# DINv2_1.net
KiCad netlist of a schematic drawn in EAGLE
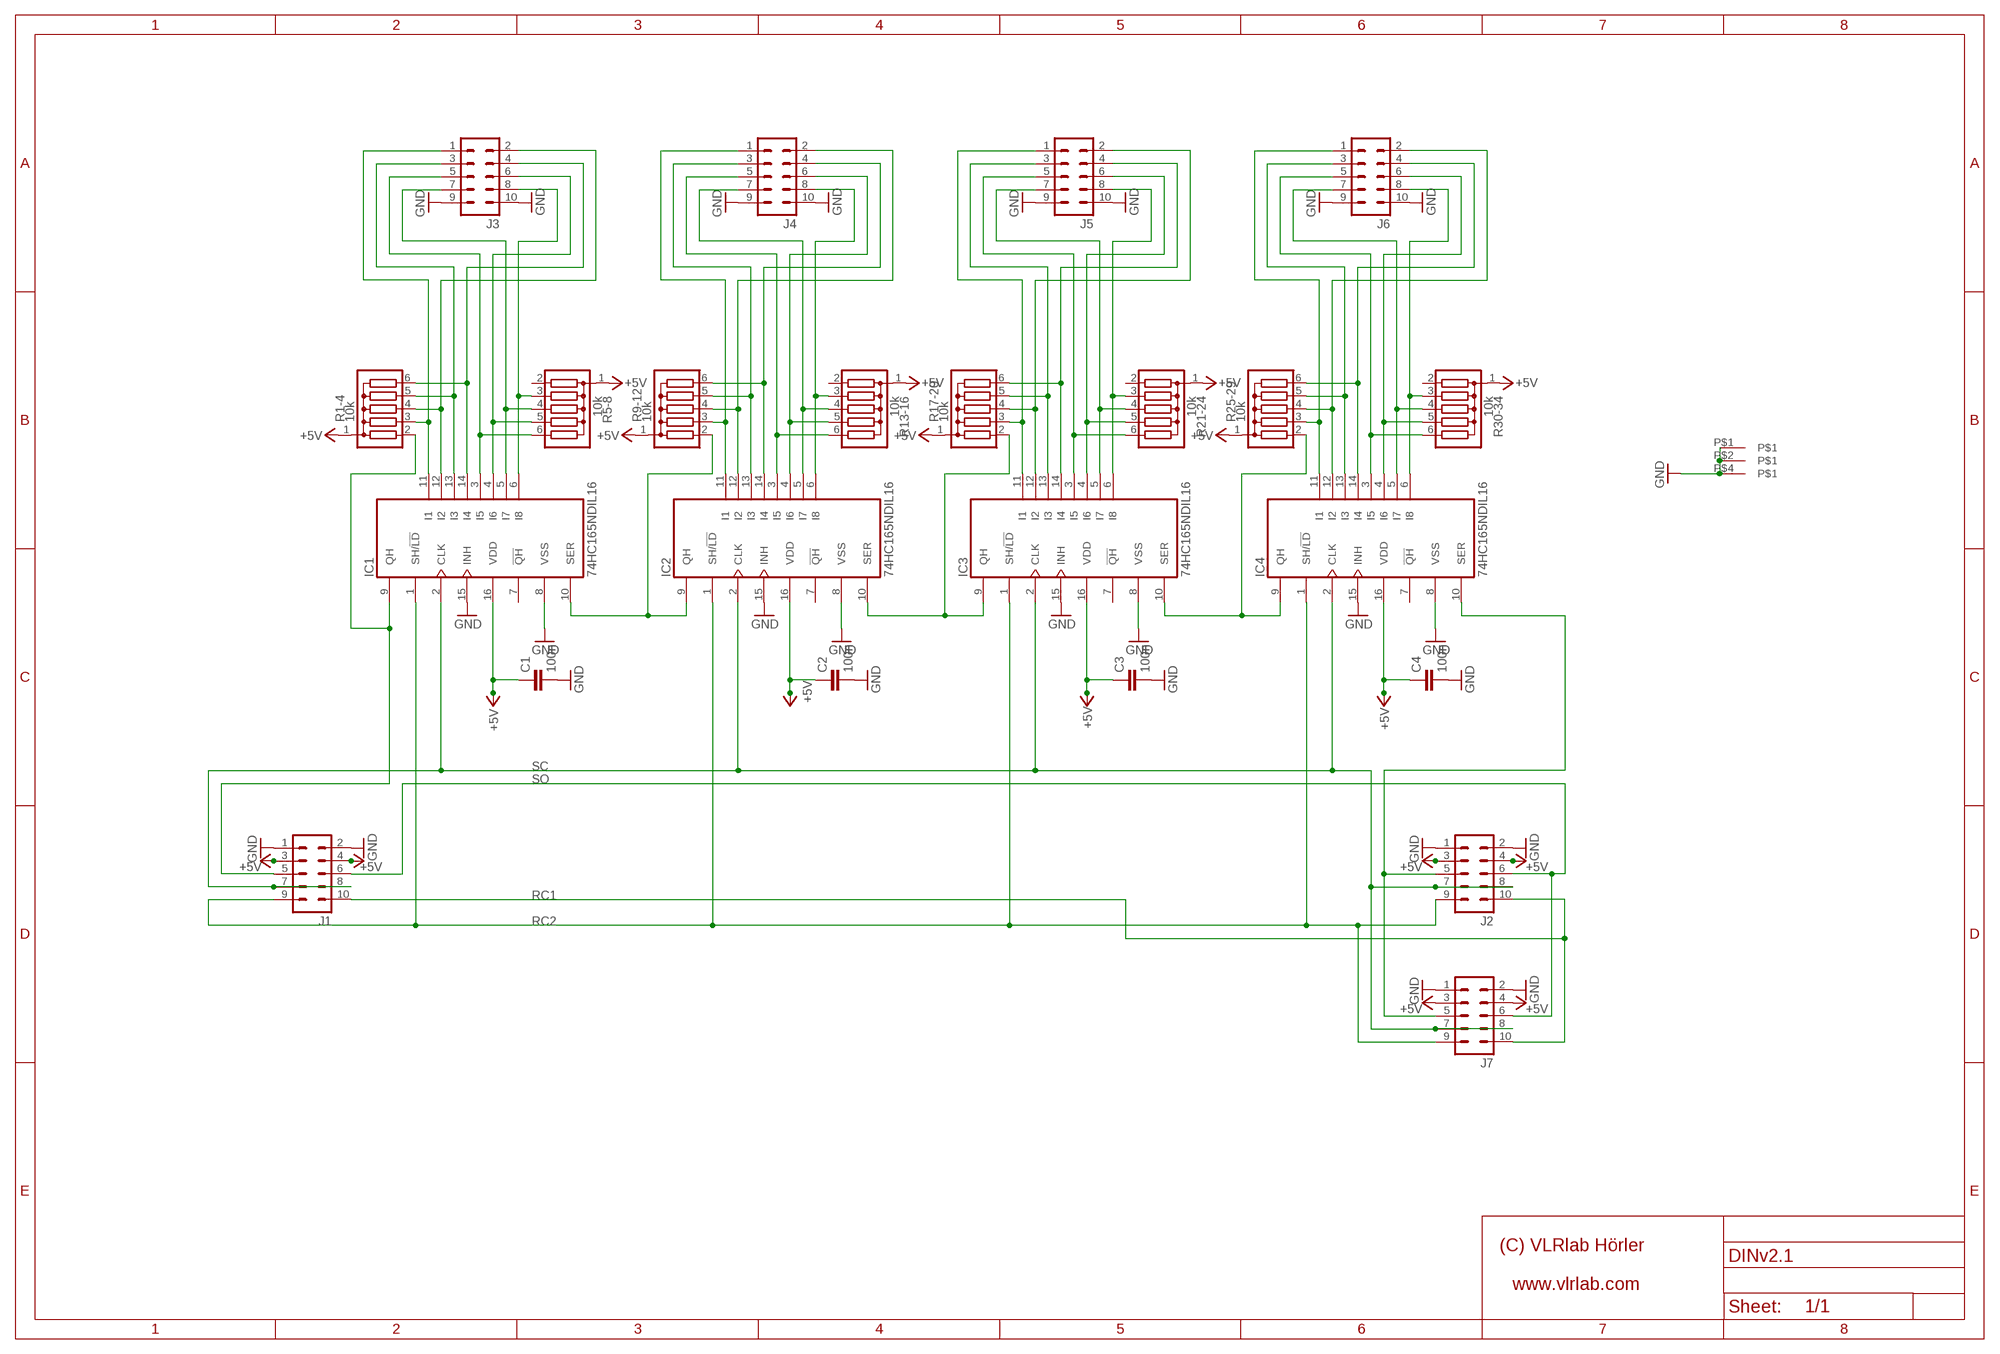
[diagram p0: schematic, sheet 1]

(export (version "E")
  (design (tool "Eeschema 10.0.6"))
  (components
    (comp (ref "C1")
      (value "100n")
      (footprint "eagle-import:C025-025X050")
      (libsource (lib "eagle-import") (part "C-EU025-025X050"))
    )
    (comp (ref "C2")
      (value "100n")
      (footprint "eagle-import:C025-025X050")
      (libsource (lib "eagle-import") (part "C-EU025-025X050"))
    )
    (comp (ref "C3")
      (value "100n")
      (footprint "eagle-import:C025-025X050")
      (libsource (lib "eagle-import") (part "C-EU025-025X050"))
    )
    (comp (ref "C4")
      (value "100n")
      (footprint "eagle-import:C025-025X050")
      (libsource (lib "eagle-import") (part "C-EU025-025X050"))
    )
    (comp (ref "IC1")
      (value "74HC165NDIL16")
      (footprint "eagle-import:DIL16")
      (libsource (lib "eagle-import") (part "74HC165NDIL16"))
    )
    (comp (ref "IC2")
      (value "74HC165NDIL16")
      (footprint "eagle-import:DIL16")
      (libsource (lib "eagle-import") (part "74HC165NDIL16"))
    )
    (comp (ref "IC3")
      (value "74HC165NDIL16")
      (footprint "eagle-import:DIL16")
      (libsource (lib "eagle-import") (part "74HC165NDIL16"))
    )
    (comp (ref "IC4")
      (value "74HC165NDIL16")
      (footprint "eagle-import:DIL16")
      (libsource (lib "eagle-import") (part "74HC165NDIL16"))
    )
    (comp (ref "J1")
      (value "ML10")
      (footprint "eagle-import:ML10")
      (libsource (lib "eagle-import") (part "ML10"))
    )
    (comp (ref "J2")
      (value "ML10")
      (footprint "eagle-import:ML10")
      (libsource (lib "eagle-import") (part "ML10"))
    )
    (comp (ref "J3")
      (value "ML10")
      (footprint "eagle-import:ML10")
      (libsource (lib "eagle-import") (part "ML10"))
    )
    (comp (ref "J4")
      (value "ML10")
      (footprint "eagle-import:ML10")
      (libsource (lib "eagle-import") (part "ML10"))
    )
    (comp (ref "J5")
      (value "ML10")
      (footprint "eagle-import:ML10")
      (libsource (lib "eagle-import") (part "ML10"))
    )
    (comp (ref "J6")
      (value "ML10")
      (footprint "eagle-import:ML10")
      (libsource (lib "eagle-import") (part "ML10"))
    )
    (comp (ref "J7")
      (value "ML10")
      (footprint "eagle-import:ML10")
      (libsource (lib "eagle-import") (part "ML10"))
    )
    (comp (ref "R1-4")
      (value "10k")
      (footprint "eagle-import:SIL6")
      (libsource (lib "eagle-import") (part "4306R"))
    )
    (comp (ref "R5-8")
      (value "10k")
      (footprint "eagle-import:SIL6")
      (libsource (lib "eagle-import") (part "4306R"))
    )
    (comp (ref "R9-12")
      (value "10k")
      (footprint "eagle-import:SIL6")
      (libsource (lib "eagle-import") (part "4306R"))
    )
    (comp (ref "R13-16")
      (value "10k")
      (footprint "eagle-import:SIL6")
      (libsource (lib "eagle-import") (part "4306R"))
    )
    (comp (ref "R17-20")
      (value "10k")
      (footprint "eagle-import:SIL6")
      (libsource (lib "eagle-import") (part "4306R"))
    )
    (comp (ref "R21-24")
      (value "10k")
      (footprint "eagle-import:SIL6")
      (libsource (lib "eagle-import") (part "4306R"))
    )
    (comp (ref "R25-29")
      (value "10k")
      (footprint "eagle-import:SIL6")
      (libsource (lib "eagle-import") (part "4306R"))
    )
    (comp (ref "R30-34")
      (value "10k")
      (footprint "eagle-import:SIL6")
      (libsource (lib "eagle-import") (part "4306R"))
    )
    (comp (ref "U$7")
      (value "MIDIBOX_HALF")
      (footprint "eagle-import:MIDIBOX14X6")
      (libsource (lib "eagle-import") (part "MIDIBOX_HALF"))
    )
  )
  (nets
    (net (code "1") (name "+5V") (class "Default")
      (node (ref "C1") (pin "1") (pinfunction "1_1") (pintype "passive"))
      (node (ref "C2") (pin "1") (pinfunction "1_1") (pintype "passive"))
      (node (ref "C3") (pin "1") (pinfunction "1_1") (pintype "passive"))
      (node (ref "C4") (pin "1") (pinfunction "1_1") (pintype "passive"))
      (node (ref "IC1") (pin "16") (pinfunction "VDD_16") (pintype "power_in"))
      (node (ref "IC2") (pin "16") (pinfunction "VDD_16") (pintype "power_in"))
      (node (ref "IC3") (pin "16") (pinfunction "VDD_16") (pintype "power_in"))
      (node (ref "IC4") (pin "16") (pinfunction "VDD_16") (pintype "power_in"))
      (node (ref "J1") (pin "3") (pinfunction "3_3") (pintype "passive"))
      (node (ref "J1") (pin "4") (pinfunction "4_4") (pintype "passive"))
      (node (ref "J2") (pin "3") (pinfunction "3_3") (pintype "passive"))
      (node (ref "J2") (pin "4") (pinfunction "4_4") (pintype "passive"))
      (node (ref "J7") (pin "3") (pinfunction "3_3") (pintype "passive"))
      (node (ref "J7") (pin "4") (pinfunction "4_4") (pintype "passive"))
      (node (ref "R1-4") (pin "1") (pinfunction "1_1") (pintype "passive"))
      (node (ref "R13-16") (pin "1") (pinfunction "1_1") (pintype "passive"))
      (node (ref "R17-20") (pin "1") (pinfunction "1_1") (pintype "passive"))
      (node (ref "R21-24") (pin "1") (pinfunction "1_1") (pintype "passive"))
      (node (ref "R25-29") (pin "1") (pinfunction "1_1") (pintype "passive"))
      (node (ref "R30-34") (pin "1") (pinfunction "1_1") (pintype "passive"))
      (node (ref "R5-8") (pin "1") (pinfunction "1_1") (pintype "passive"))
      (node (ref "R9-12") (pin "1") (pinfunction "1_1") (pintype "passive"))
    )
    (net (code "2") (name "/RC1") (class "Default")
      (node (ref "J1") (pin "10") (pinfunction "10_10") (pintype "passive"))
      (node (ref "J2") (pin "10") (pinfunction "10_10") (pintype "passive"))
      (node (ref "J7") (pin "10") (pinfunction "10_10") (pintype "passive"))
    )
    (net (code "3") (name "/RC2") (class "Default")
      (node (ref "IC1") (pin "1") (pinfunction "SH/~{LD}_1") (pintype "input"))
      (node (ref "IC2") (pin "1") (pinfunction "SH/~{LD}_1") (pintype "input"))
      (node (ref "IC3") (pin "1") (pinfunction "SH/~{LD}_1") (pintype "input"))
      (node (ref "IC4") (pin "1") (pinfunction "SH/~{LD}_1") (pintype "input"))
      (node (ref "J1") (pin "9") (pinfunction "9_9") (pintype "passive"))
      (node (ref "J2") (pin "9") (pinfunction "9_9") (pintype "passive"))
      (node (ref "J7") (pin "9") (pinfunction "9_9") (pintype "passive"))
    )
    (net (code "4") (name "/SC") (class "Default")
      (node (ref "IC1") (pin "2") (pinfunction "CLK_2") (pintype "input"))
      (node (ref "IC2") (pin "2") (pinfunction "CLK_2") (pintype "input"))
      (node (ref "IC3") (pin "2") (pinfunction "CLK_2") (pintype "input"))
      (node (ref "IC4") (pin "2") (pinfunction "CLK_2") (pintype "input"))
      (node (ref "J1") (pin "7") (pinfunction "7_7") (pintype "passive"))
      (node (ref "J1") (pin "8") (pinfunction "8_8") (pintype "passive"))
      (node (ref "J2") (pin "7") (pinfunction "7_7") (pintype "passive"))
      (node (ref "J2") (pin "8") (pinfunction "8_8") (pintype "passive"))
      (node (ref "J7") (pin "7") (pinfunction "7_7") (pintype "passive"))
      (node (ref "J7") (pin "8") (pinfunction "8_8") (pintype "passive"))
    )
    (net (code "5") (name "/SO") (class "Default")
      (node (ref "J1") (pin "6") (pinfunction "6_6") (pintype "passive"))
      (node (ref "J2") (pin "6") (pinfunction "6_6") (pintype "passive"))
      (node (ref "J7") (pin "6") (pinfunction "6_6") (pintype "passive"))
    )
    (net (code "6") (name "GND") (class "Default")
      (node (ref "C1") (pin "2") (pinfunction "2_2") (pintype "passive"))
      (node (ref "C2") (pin "2") (pinfunction "2_2") (pintype "passive"))
      (node (ref "C3") (pin "2") (pinfunction "2_2") (pintype "passive"))
      (node (ref "C4") (pin "2") (pinfunction "2_2") (pintype "passive"))
      (node (ref "IC1") (pin "15") (pinfunction "INH_15") (pintype "input"))
      (node (ref "IC1") (pin "8") (pinfunction "VSS_8") (pintype "power_in"))
      (node (ref "IC2") (pin "15") (pinfunction "INH_15") (pintype "input"))
      (node (ref "IC2") (pin "8") (pinfunction "VSS_8") (pintype "power_in"))
      (node (ref "IC3") (pin "15") (pinfunction "INH_15") (pintype "input"))
      (node (ref "IC3") (pin "8") (pinfunction "VSS_8") (pintype "power_in"))
      (node (ref "IC4") (pin "15") (pinfunction "INH_15") (pintype "input"))
      (node (ref "IC4") (pin "8") (pinfunction "VSS_8") (pintype "power_in"))
      (node (ref "J1") (pin "1") (pinfunction "1_1") (pintype "passive"))
      (node (ref "J1") (pin "2") (pinfunction "2_2") (pintype "passive"))
      (node (ref "J2") (pin "1") (pinfunction "1_1") (pintype "passive"))
      (node (ref "J2") (pin "2") (pinfunction "2_2") (pintype "passive"))
      (node (ref "J3") (pin "10") (pinfunction "10_10") (pintype "passive"))
      (node (ref "J3") (pin "9") (pinfunction "9_9") (pintype "passive"))
      (node (ref "J4") (pin "10") (pinfunction "10_10") (pintype "passive"))
      (node (ref "J4") (pin "9") (pinfunction "9_9") (pintype "passive"))
      (node (ref "J5") (pin "10") (pinfunction "10_10") (pintype "passive"))
      (node (ref "J5") (pin "9") (pinfunction "9_9") (pintype "passive"))
      (node (ref "J6") (pin "10") (pinfunction "10_10") (pintype "passive"))
      (node (ref "J6") (pin "9") (pinfunction "9_9") (pintype "passive"))
      (node (ref "J7") (pin "1") (pinfunction "1_1") (pintype "passive"))
      (node (ref "J7") (pin "2") (pinfunction "2_2") (pintype "passive"))
      (node (ref "U$7") (pin "P$1") (pinfunction "P$1_P$1") (pintype "bidirectional"))
      (node (ref "U$7") (pin "P$2") (pinfunction "P$1_P$2") (pintype "bidirectional"))
      (node (ref "U$7") (pin "P$4") (pinfunction "P$1_P$4") (pintype "bidirectional"))
    )
    (net (code "7") (name "Net-(IC1-I1)") (class "Default")
      (node (ref "IC1") (pin "11") (pinfunction "I1_11") (pintype "input"))
      (node (ref "J3") (pin "1") (pinfunction "1_1") (pintype "passive"))
      (node (ref "R1-4") (pin "3") (pinfunction "3_3") (pintype "passive"))
    )
    (net (code "8") (name "Net-(IC1-I2)") (class "Default")
      (node (ref "IC1") (pin "12") (pinfunction "I2_12") (pintype "input"))
      (node (ref "J3") (pin "2") (pinfunction "2_2") (pintype "passive"))
      (node (ref "R1-4") (pin "4") (pinfunction "4_4") (pintype "passive"))
    )
    (net (code "9") (name "Net-(IC1-I3)") (class "Default")
      (node (ref "IC1") (pin "13") (pinfunction "I3_13") (pintype "input"))
      (node (ref "J3") (pin "3") (pinfunction "3_3") (pintype "passive"))
      (node (ref "R1-4") (pin "5") (pinfunction "5_5") (pintype "passive"))
    )
    (net (code "10") (name "Net-(IC1-I4)") (class "Default")
      (node (ref "IC1") (pin "14") (pinfunction "I4_14") (pintype "input"))
      (node (ref "J3") (pin "4") (pinfunction "4_4") (pintype "passive"))
      (node (ref "R1-4") (pin "6") (pinfunction "6_6") (pintype "passive"))
    )
    (net (code "11") (name "Net-(IC1-I5)") (class "Default")
      (node (ref "IC1") (pin "3") (pinfunction "I5_3") (pintype "input"))
      (node (ref "J3") (pin "5") (pinfunction "5_5") (pintype "passive"))
      (node (ref "R5-8") (pin "6") (pinfunction "6_6") (pintype "passive"))
    )
    (net (code "12") (name "Net-(IC1-I6)") (class "Default")
      (node (ref "IC1") (pin "4") (pinfunction "I6_4") (pintype "input"))
      (node (ref "J3") (pin "6") (pinfunction "6_6") (pintype "passive"))
      (node (ref "R5-8") (pin "5") (pinfunction "5_5") (pintype "passive"))
    )
    (net (code "13") (name "Net-(IC1-I7)") (class "Default")
      (node (ref "IC1") (pin "5") (pinfunction "I7_5") (pintype "input"))
      (node (ref "J3") (pin "7") (pinfunction "7_7") (pintype "passive"))
      (node (ref "R5-8") (pin "4") (pinfunction "4_4") (pintype "passive"))
    )
    (net (code "14") (name "Net-(IC1-I8)") (class "Default")
      (node (ref "IC1") (pin "6") (pinfunction "I8_6") (pintype "input"))
      (node (ref "J3") (pin "8") (pinfunction "8_8") (pintype "passive"))
      (node (ref "R5-8") (pin "3") (pinfunction "3_3") (pintype "passive"))
    )
    (net (code "15") (name "Net-(IC1-QH)") (class "Default")
      (node (ref "IC1") (pin "9") (pinfunction "QH_9") (pintype "output"))
      (node (ref "J1") (pin "5") (pinfunction "5_5") (pintype "passive"))
      (node (ref "R1-4") (pin "2") (pinfunction "2_2") (pintype "passive"))
    )
    (net (code "16") (name "Net-(IC1-SER)") (class "Default")
      (node (ref "IC1") (pin "10") (pinfunction "SER_10") (pintype "input"))
      (node (ref "IC2") (pin "9") (pinfunction "QH_9") (pintype "output"))
      (node (ref "R9-12") (pin "2") (pinfunction "2_2") (pintype "passive"))
    )
    (net (code "17") (name "Net-(IC2-I1)") (class "Default")
      (node (ref "IC2") (pin "11") (pinfunction "I1_11") (pintype "input"))
      (node (ref "J4") (pin "1") (pinfunction "1_1") (pintype "passive"))
      (node (ref "R9-12") (pin "3") (pinfunction "3_3") (pintype "passive"))
    )
    (net (code "18") (name "Net-(IC2-I2)") (class "Default")
      (node (ref "IC2") (pin "12") (pinfunction "I2_12") (pintype "input"))
      (node (ref "J4") (pin "2") (pinfunction "2_2") (pintype "passive"))
      (node (ref "R9-12") (pin "4") (pinfunction "4_4") (pintype "passive"))
    )
    (net (code "19") (name "Net-(IC2-I3)") (class "Default")
      (node (ref "IC2") (pin "13") (pinfunction "I3_13") (pintype "input"))
      (node (ref "J4") (pin "3") (pinfunction "3_3") (pintype "passive"))
      (node (ref "R9-12") (pin "5") (pinfunction "5_5") (pintype "passive"))
    )
    (net (code "20") (name "Net-(IC2-I4)") (class "Default")
      (node (ref "IC2") (pin "14") (pinfunction "I4_14") (pintype "input"))
      (node (ref "J4") (pin "4") (pinfunction "4_4") (pintype "passive"))
      (node (ref "R9-12") (pin "6") (pinfunction "6_6") (pintype "passive"))
    )
    (net (code "21") (name "Net-(IC2-I5)") (class "Default")
      (node (ref "IC2") (pin "3") (pinfunction "I5_3") (pintype "input"))
      (node (ref "J4") (pin "5") (pinfunction "5_5") (pintype "passive"))
      (node (ref "R13-16") (pin "6") (pinfunction "6_6") (pintype "passive"))
    )
    (net (code "22") (name "Net-(IC2-I6)") (class "Default")
      (node (ref "IC2") (pin "4") (pinfunction "I6_4") (pintype "input"))
      (node (ref "J4") (pin "6") (pinfunction "6_6") (pintype "passive"))
      (node (ref "R13-16") (pin "5") (pinfunction "5_5") (pintype "passive"))
    )
    (net (code "23") (name "Net-(IC2-I7)") (class "Default")
      (node (ref "IC2") (pin "5") (pinfunction "I7_5") (pintype "input"))
      (node (ref "J4") (pin "7") (pinfunction "7_7") (pintype "passive"))
      (node (ref "R13-16") (pin "4") (pinfunction "4_4") (pintype "passive"))
    )
    (net (code "24") (name "Net-(IC2-I8)") (class "Default")
      (node (ref "IC2") (pin "6") (pinfunction "I8_6") (pintype "input"))
      (node (ref "J4") (pin "8") (pinfunction "8_8") (pintype "passive"))
      (node (ref "R13-16") (pin "3") (pinfunction "3_3") (pintype "passive"))
    )
    (net (code "25") (name "Net-(IC2-SER)") (class "Default")
      (node (ref "IC2") (pin "10") (pinfunction "SER_10") (pintype "input"))
      (node (ref "IC3") (pin "9") (pinfunction "QH_9") (pintype "output"))
      (node (ref "R17-20") (pin "2") (pinfunction "2_2") (pintype "passive"))
    )
    (net (code "26") (name "Net-(IC3-I1)") (class "Default")
      (node (ref "IC3") (pin "11") (pinfunction "I1_11") (pintype "input"))
      (node (ref "J5") (pin "1") (pinfunction "1_1") (pintype "passive"))
      (node (ref "R17-20") (pin "3") (pinfunction "3_3") (pintype "passive"))
    )
    (net (code "27") (name "Net-(IC3-I2)") (class "Default")
      (node (ref "IC3") (pin "12") (pinfunction "I2_12") (pintype "input"))
      (node (ref "J5") (pin "2") (pinfunction "2_2") (pintype "passive"))
      (node (ref "R17-20") (pin "4") (pinfunction "4_4") (pintype "passive"))
    )
    (net (code "28") (name "Net-(IC3-I3)") (class "Default")
      (node (ref "IC3") (pin "13") (pinfunction "I3_13") (pintype "input"))
      (node (ref "J5") (pin "3") (pinfunction "3_3") (pintype "passive"))
      (node (ref "R17-20") (pin "5") (pinfunction "5_5") (pintype "passive"))
    )
    (net (code "29") (name "Net-(IC3-I4)") (class "Default")
      (node (ref "IC3") (pin "14") (pinfunction "I4_14") (pintype "input"))
      (node (ref "J5") (pin "4") (pinfunction "4_4") (pintype "passive"))
      (node (ref "R17-20") (pin "6") (pinfunction "6_6") (pintype "passive"))
    )
    (net (code "30") (name "Net-(IC3-I5)") (class "Default")
      (node (ref "IC3") (pin "3") (pinfunction "I5_3") (pintype "input"))
      (node (ref "J5") (pin "5") (pinfunction "5_5") (pintype "passive"))
      (node (ref "R21-24") (pin "6") (pinfunction "6_6") (pintype "passive"))
    )
    (net (code "31") (name "Net-(IC3-I6)") (class "Default")
      (node (ref "IC3") (pin "4") (pinfunction "I6_4") (pintype "input"))
      (node (ref "J5") (pin "6") (pinfunction "6_6") (pintype "passive"))
      (node (ref "R21-24") (pin "5") (pinfunction "5_5") (pintype "passive"))
    )
    (net (code "32") (name "Net-(IC3-I7)") (class "Default")
      (node (ref "IC3") (pin "5") (pinfunction "I7_5") (pintype "input"))
      (node (ref "J5") (pin "7") (pinfunction "7_7") (pintype "passive"))
      (node (ref "R21-24") (pin "4") (pinfunction "4_4") (pintype "passive"))
    )
    (net (code "33") (name "Net-(IC3-I8)") (class "Default")
      (node (ref "IC3") (pin "6") (pinfunction "I8_6") (pintype "input"))
      (node (ref "J5") (pin "8") (pinfunction "8_8") (pintype "passive"))
      (node (ref "R21-24") (pin "3") (pinfunction "3_3") (pintype "passive"))
    )
    (net (code "34") (name "Net-(IC3-SER)") (class "Default")
      (node (ref "IC3") (pin "10") (pinfunction "SER_10") (pintype "input"))
      (node (ref "IC4") (pin "9") (pinfunction "QH_9") (pintype "output"))
      (node (ref "R25-29") (pin "2") (pinfunction "2_2") (pintype "passive"))
    )
    (net (code "35") (name "Net-(IC4-I1)") (class "Default")
      (node (ref "IC4") (pin "11") (pinfunction "I1_11") (pintype "input"))
      (node (ref "J6") (pin "1") (pinfunction "1_1") (pintype "passive"))
      (node (ref "R25-29") (pin "3") (pinfunction "3_3") (pintype "passive"))
    )
    (net (code "36") (name "Net-(IC4-I2)") (class "Default")
      (node (ref "IC4") (pin "12") (pinfunction "I2_12") (pintype "input"))
      (node (ref "J6") (pin "2") (pinfunction "2_2") (pintype "passive"))
      (node (ref "R25-29") (pin "4") (pinfunction "4_4") (pintype "passive"))
    )
    (net (code "37") (name "Net-(IC4-I3)") (class "Default")
      (node (ref "IC4") (pin "13") (pinfunction "I3_13") (pintype "input"))
      (node (ref "J6") (pin "3") (pinfunction "3_3") (pintype "passive"))
      (node (ref "R25-29") (pin "5") (pinfunction "5_5") (pintype "passive"))
    )
    (net (code "38") (name "Net-(IC4-I4)") (class "Default")
      (node (ref "IC4") (pin "14") (pinfunction "I4_14") (pintype "input"))
      (node (ref "J6") (pin "4") (pinfunction "4_4") (pintype "passive"))
      (node (ref "R25-29") (pin "6") (pinfunction "6_6") (pintype "passive"))
    )
    (net (code "39") (name "Net-(IC4-I5)") (class "Default")
      (node (ref "IC4") (pin "3") (pinfunction "I5_3") (pintype "input"))
      (node (ref "J6") (pin "5") (pinfunction "5_5") (pintype "passive"))
      (node (ref "R30-34") (pin "6") (pinfunction "6_6") (pintype "passive"))
    )
    (net (code "40") (name "Net-(IC4-I6)") (class "Default")
      (node (ref "IC4") (pin "4") (pinfunction "I6_4") (pintype "input"))
      (node (ref "J6") (pin "6") (pinfunction "6_6") (pintype "passive"))
      (node (ref "R30-34") (pin "5") (pinfunction "5_5") (pintype "passive"))
    )
    (net (code "41") (name "Net-(IC4-I7)") (class "Default")
      (node (ref "IC4") (pin "5") (pinfunction "I7_5") (pintype "input"))
      (node (ref "J6") (pin "7") (pinfunction "7_7") (pintype "passive"))
      (node (ref "R30-34") (pin "4") (pinfunction "4_4") (pintype "passive"))
    )
    (net (code "42") (name "Net-(IC4-I8)") (class "Default")
      (node (ref "IC4") (pin "6") (pinfunction "I8_6") (pintype "input"))
      (node (ref "J6") (pin "8") (pinfunction "8_8") (pintype "passive"))
      (node (ref "R30-34") (pin "3") (pinfunction "3_3") (pintype "passive"))
    )
    (net (code "43") (name "Net-(IC4-SER)") (class "Default")
      (node (ref "IC4") (pin "10") (pinfunction "SER_10") (pintype "input"))
      (node (ref "J2") (pin "5") (pinfunction "5_5") (pintype "passive"))
      (node (ref "J7") (pin "5") (pinfunction "5_5") (pintype "passive"))
    )
    (net (code "44") (name "unconnected-(IC1-~{QH}-Pad7)") (class "Default")
      (node (ref "IC1") (pin "7") (pinfunction "~{QH}_7") (pintype "output"))
    )
    (net (code "45") (name "unconnected-(IC2-~{QH}-Pad7)") (class "Default")
      (node (ref "IC2") (pin "7") (pinfunction "~{QH}_7") (pintype "output"))
    )
    (net (code "46") (name "unconnected-(IC3-~{QH}-Pad7)") (class "Default")
      (node (ref "IC3") (pin "7") (pinfunction "~{QH}_7") (pintype "output"))
    )
    (net (code "47") (name "unconnected-(IC4-~{QH}-Pad7)") (class "Default")
      (node (ref "IC4") (pin "7") (pinfunction "~{QH}_7") (pintype "output"))
    )
    (net (code "48") (name "unconnected-(R5-8-Pad2)") (class "Default")
      (node (ref "R5-8") (pin "2") (pinfunction "2_2") (pintype "passive"))
    )
    (net (code "49") (name "unconnected-(R13-16-Pad2)") (class "Default")
      (node (ref "R13-16") (pin "2") (pinfunction "2_2") (pintype "passive"))
    )
    (net (code "50") (name "unconnected-(R21-24-Pad2)") (class "Default")
      (node (ref "R21-24") (pin "2") (pinfunction "2_2") (pintype "passive"))
    )
    (net (code "51") (name "unconnected-(R30-34-Pad2)") (class "Default")
      (node (ref "R30-34") (pin "2") (pinfunction "2_2") (pintype "passive"))
    )
  )
)
